# 2024_01_03_bar_IO_module.net
KiCad netlist of a schematic drawn in EasyEDA Pro
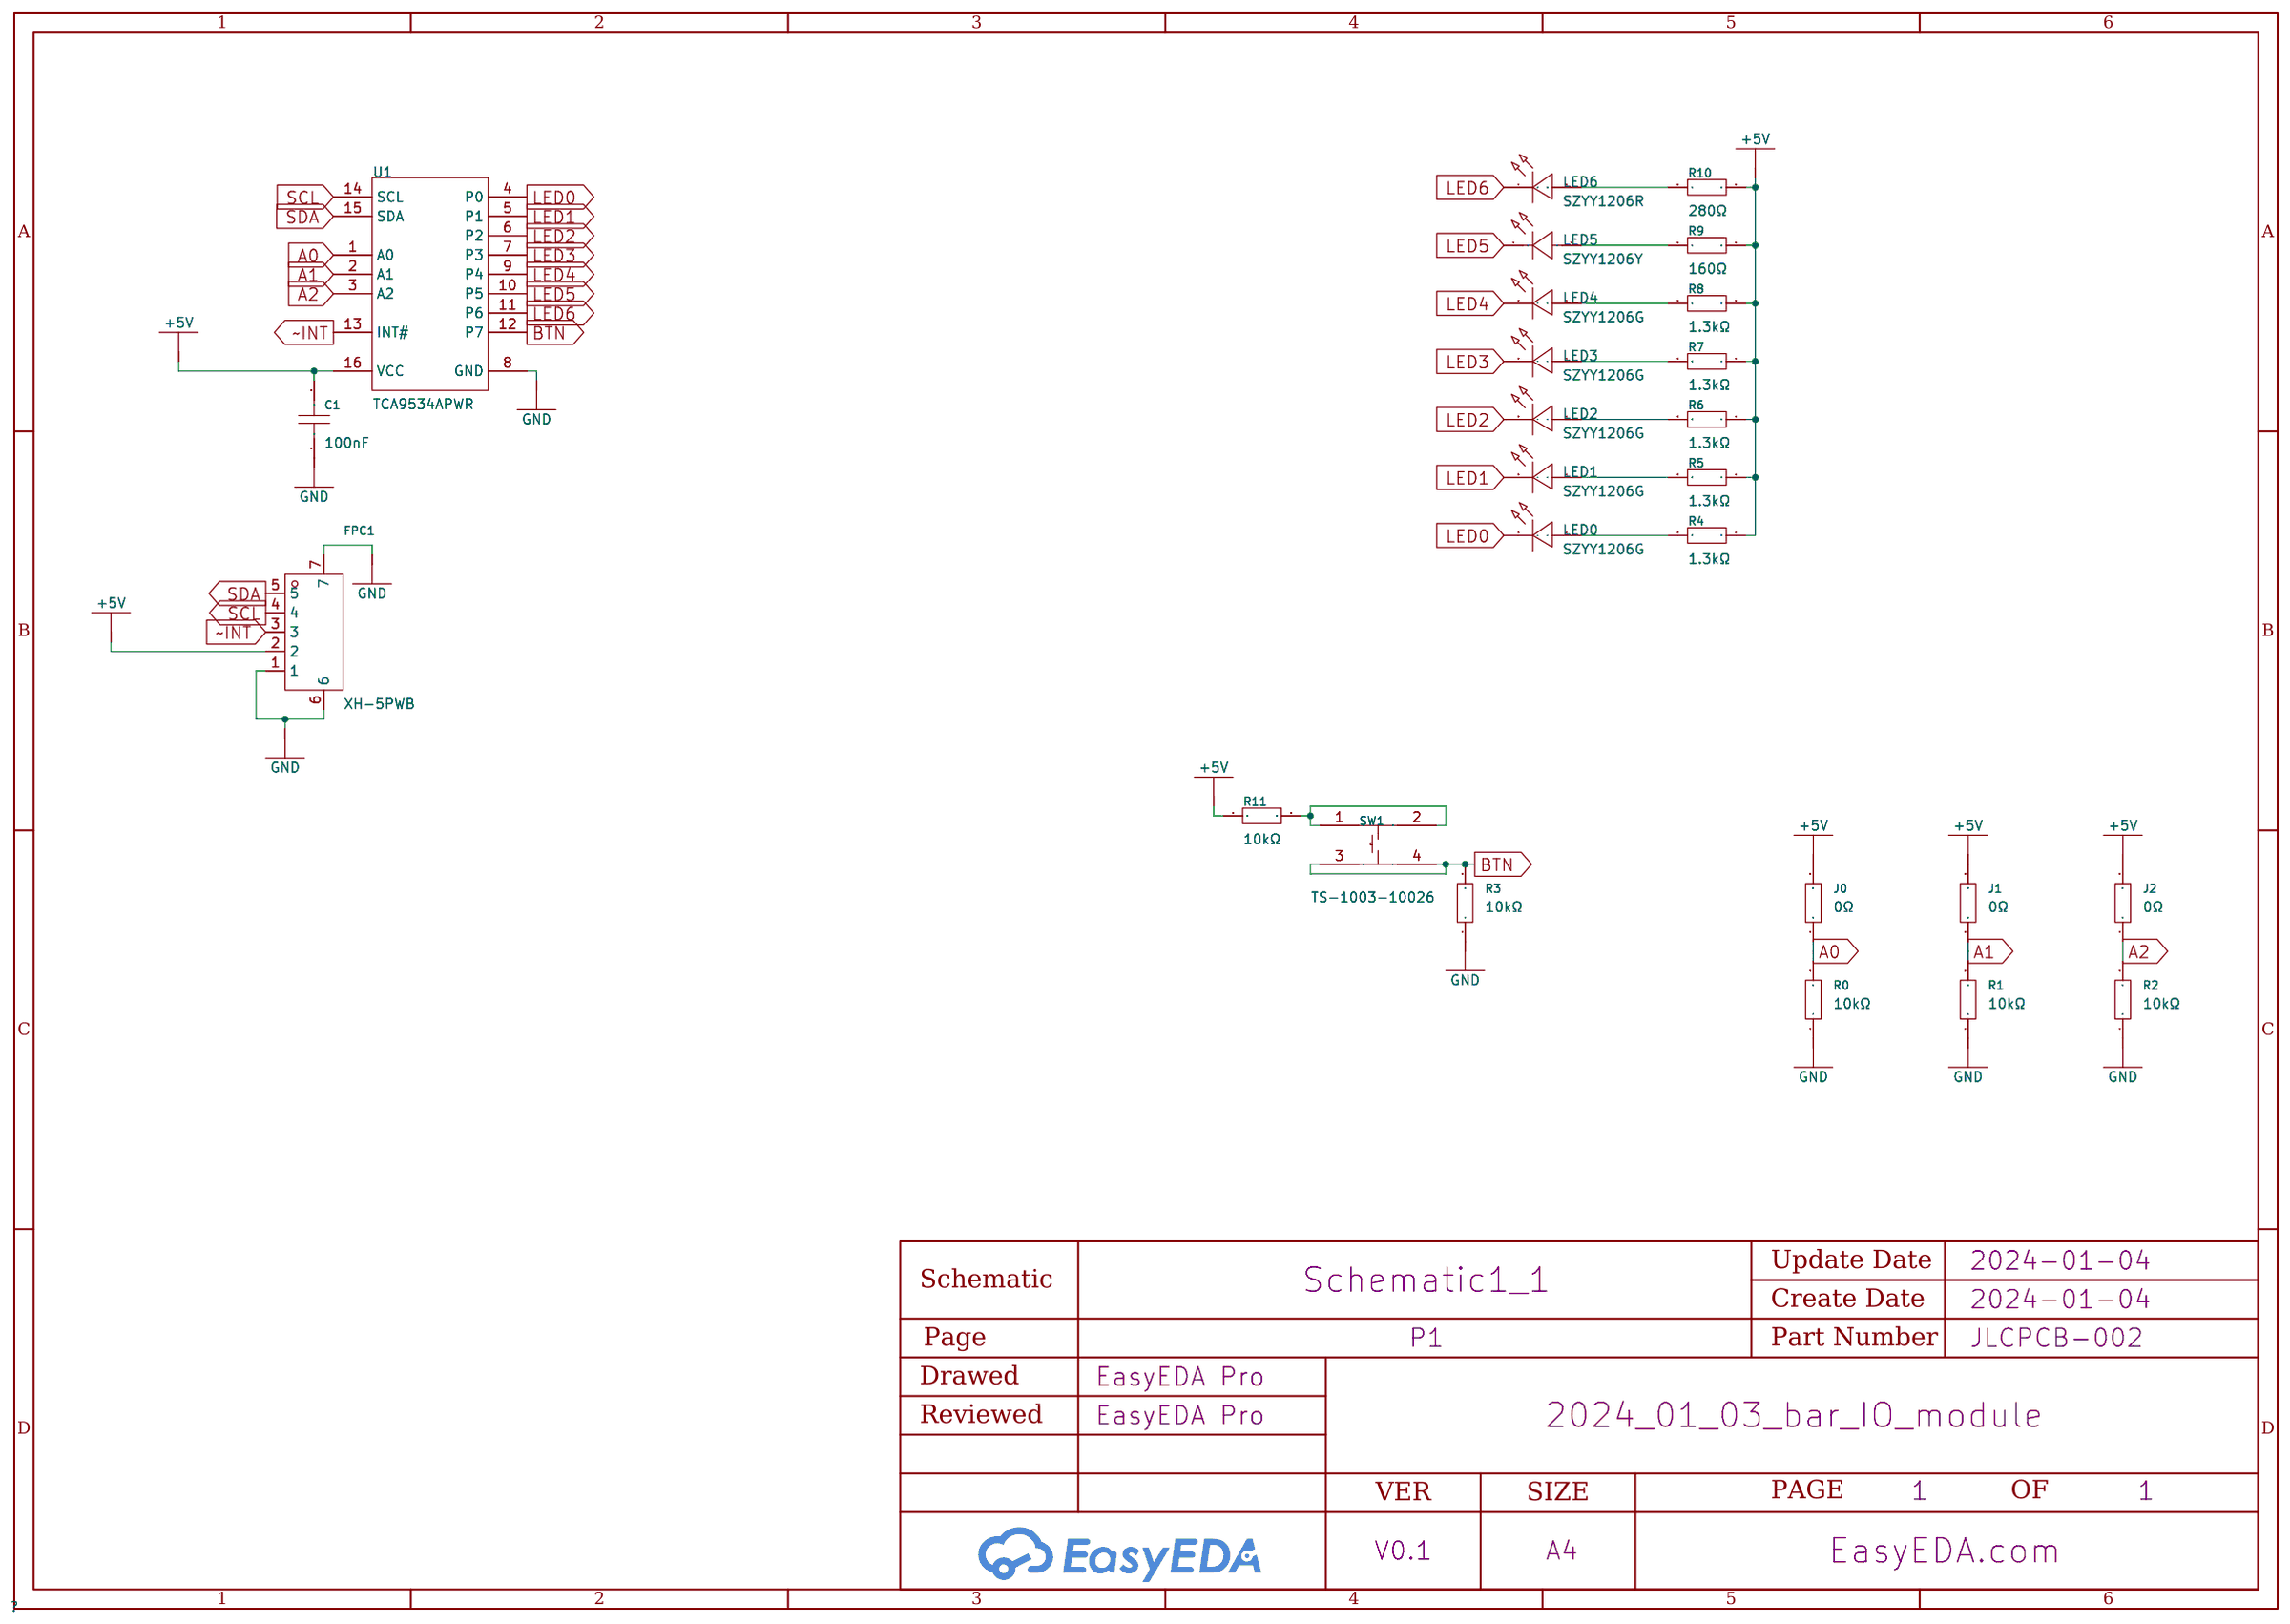
[diagram p0: schematic sheet]

(export (version "E")
  (design (tool "Eeschema 10.0.6"))
  (components
    (comp (ref "C1")
      (value "100nF")
      (footprint "easyedapro:C0603")
      (fields
        (field (name "Manufacturer Part") "HMK107B7104KAHT")
        (field (name "Manufacturer") "TAIYO YUDEN(太诱)")
      )
      (libsource (lib "easyedapro") (part "HMK107B7104KAHT"))
    )
    (comp (ref "FPC1")
      (value "XH-5PWB")
      (footprint "easyedapro:CONN-SMD_5P-P2.50_DEALON_XH-5PWB")
      (fields (field (name "Manufacturer") "DEALON(德艺隆)"))
      (libsource (lib "easyedapro") (part "XH-5PWB"))
    )
    (comp (ref "J0")
      (value "0Ω")
      (footprint "easyedapro:R0805")
      (fields
        (field (name "Manufacturer Part") "0805W8F1002T5E")
        (field (name "Manufacturer") "UNI-ROYAL(厚声)")
      )
      (libsource (lib "easyedapro") (part "0805W8F1002T5E"))
    )
    (comp (ref "J1")
      (value "0Ω")
      (footprint "easyedapro:R0805")
      (fields
        (field (name "Manufacturer Part") "0805W8F1002T5E")
        (field (name "Manufacturer") "UNI-ROYAL(厚声)")
      )
      (libsource (lib "easyedapro") (part "0805W8F1002T5E"))
    )
    (comp (ref "J2")
      (value "0Ω")
      (footprint "easyedapro:R0805")
      (fields
        (field (name "Manufacturer Part") "0805W8F1002T5E")
        (field (name "Manufacturer") "UNI-ROYAL(厚声)")
      )
      (libsource (lib "easyedapro") (part "0805W8F1002T5E"))
    )
    (comp (ref "LED0")
      (value "SZYY1206G")
      (footprint "easyedapro:LED1206-R-RD")
      (description "Emitted Color:Emerald")
      (fields (field (name "Manufacturer") "yongyu(永裕光电)"))
      (libsource (lib "easyedapro") (part "SZYY1206G"))
    )
    (comp (ref "LED1")
      (value "SZYY1206G")
      (footprint "easyedapro:LED1206-R-RD")
      (description "Emitted Color:Emerald")
      (fields (field (name "Manufacturer") "yongyu(永裕光电)"))
      (libsource (lib "easyedapro") (part "SZYY1206G"))
    )
    (comp (ref "LED2")
      (value "SZYY1206G")
      (footprint "easyedapro:LED1206-R-RD")
      (description "Emitted Color:Emerald")
      (fields (field (name "Manufacturer") "yongyu(永裕光电)"))
      (libsource (lib "easyedapro") (part "SZYY1206G"))
    )
    (comp (ref "LED3")
      (value "SZYY1206G")
      (footprint "easyedapro:LED1206-R-RD")
      (description "Emitted Color:Emerald")
      (fields (field (name "Manufacturer") "yongyu(永裕光电)"))
      (libsource (lib "easyedapro") (part "SZYY1206G"))
    )
    (comp (ref "LED4")
      (value "SZYY1206G")
      (footprint "easyedapro:LED1206-R-RD")
      (description "Emitted Color:Emerald")
      (fields (field (name "Manufacturer") "yongyu(永裕光电)"))
      (libsource (lib "easyedapro") (part "SZYY1206G"))
    )
    (comp (ref "LED5")
      (value "SZYY1206Y")
      (footprint "easyedapro:LED1206-R-RD")
      (fields (field (name "Manufacturer") "yongyu(永裕光电)"))
      (libsource (lib "easyedapro") (part "SZYY1206Y"))
    )
    (comp (ref "LED6")
      (value "SZYY1206R")
      (footprint "easyedapro:LED1206-R-RD")
      (fields (field (name "Manufacturer") "yongyu(永裕光电)"))
      (libsource (lib "easyedapro") (part "SZYY1206R"))
    )
    (comp (ref "R0")
      (value "10kΩ")
      (footprint "easyedapro:R0603")
      (fields
        (field (name "Manufacturer Part") "0603WAF1002T5E")
        (field (name "Manufacturer") "UNI-ROYAL(厚声)")
      )
      (libsource (lib "easyedapro") (part "0603WAF1002T5E"))
    )
    (comp (ref "R1")
      (value "10kΩ")
      (footprint "easyedapro:R0603")
      (fields
        (field (name "Manufacturer Part") "0603WAF1002T5E")
        (field (name "Manufacturer") "UNI-ROYAL(厚声)")
      )
      (libsource (lib "easyedapro") (part "0603WAF1002T5E"))
    )
    (comp (ref "R2")
      (value "10kΩ")
      (footprint "easyedapro:R0603")
      (fields
        (field (name "Manufacturer Part") "0603WAF1002T5E")
        (field (name "Manufacturer") "UNI-ROYAL(厚声)")
      )
      (libsource (lib "easyedapro") (part "0603WAF1002T5E"))
    )
    (comp (ref "R3")
      (value "10kΩ")
      (footprint "easyedapro:R0603")
      (fields
        (field (name "Manufacturer Part") "0603WAF1002T5E")
        (field (name "Manufacturer") "UNI-ROYAL(厚声)")
      )
      (libsource (lib "easyedapro") (part "0603WAF1002T5E"))
    )
    (comp (ref "R4")
      (value "1.3kΩ")
      (footprint "easyedapro:R0603")
      (fields
        (field (name "Manufacturer Part") "CQ03WAJ0132T5E")
        (field (name "Manufacturer") "UNI-ROYAL(厚声)")
      )
      (libsource (lib "easyedapro") (part "0603WAF1002T5E"))
    )
    (comp (ref "R5")
      (value "1.3kΩ")
      (footprint "easyedapro:R0603")
      (fields
        (field (name "Manufacturer Part") "CQ03WAJ0132T5E")
        (field (name "Manufacturer") "UNI-ROYAL(厚声)")
      )
      (libsource (lib "easyedapro") (part "0603WAF1002T5E"))
    )
    (comp (ref "R6")
      (value "1.3kΩ")
      (footprint "easyedapro:R0603")
      (fields
        (field (name "Manufacturer Part") "CQ03WAJ0132T5E")
        (field (name "Manufacturer") "UNI-ROYAL(厚声)")
      )
      (libsource (lib "easyedapro") (part "0603WAF1002T5E"))
    )
    (comp (ref "R7")
      (value "1.3kΩ")
      (footprint "easyedapro:R0603")
      (fields
        (field (name "Manufacturer Part") "CQ03WAJ0132T5E")
        (field (name "Manufacturer") "UNI-ROYAL(厚声)")
      )
      (libsource (lib "easyedapro") (part "0603WAF1002T5E"))
    )
    (comp (ref "R8")
      (value "1.3kΩ")
      (footprint "easyedapro:R0603")
      (fields
        (field (name "Manufacturer Part") "CQ03WAJ0132T5E")
        (field (name "Manufacturer") "UNI-ROYAL(厚声)")
      )
      (libsource (lib "easyedapro") (part "0603WAF1002T5E"))
    )
    (comp (ref "R9")
      (value "160Ω")
      (footprint "easyedapro:R0603")
      (fields
        (field (name "Manufacturer Part") "FRC0603J161 TS")
        (field (name "Manufacturer") "UNI-ROYAL(厚声)")
      )
      (libsource (lib "easyedapro") (part "0603WAF1002T5E"))
    )
    (comp (ref "R10")
      (value "280Ω")
      (footprint "easyedapro:R0603")
      (fields (field (name "Manufacturer Part") "ARG03BTC2800") (field (name "Manufacturer") "UNI-ROYAL(厚声)"))
      (libsource (lib "easyedapro") (part "0603WAF1002T5E"))
    )
    (comp (ref "R11")
      (value "10kΩ")
      (footprint "easyedapro:R0603")
      (fields
        (field (name "Manufacturer Part") "0603WAF1002T5E")
        (field (name "Manufacturer") "UNI-ROYAL(厚声)")
      )
      (libsource (lib "easyedapro") (part "0603WAF1002T5E"))
    )
    (comp (ref "SW1")
      (value "TS-1003-10026")
      (footprint "easyedapro:SW-TH_4P-L12.0-W12.0-P5.00-LS12.5")
      (fields (field (name "Manufacturer") "XUNPU(讯普)"))
      (libsource (lib "easyedapro") (part "TS-1003-10026"))
    )
    (comp (ref "U1")
      (value "TCA9534APWR")
      (footprint "easyedapro:TSSOP-16_L5.0-W4.4-P0.65-LS6.4-BL")
      (fields (field (name "Manufacturer") "TI(德州仪器)"))
      (libsource (lib "easyedapro") (part "TCA9534APWR"))
    )
  )
  (nets
    (net (code "1") (name "+5V") (class "Default")
      (node (ref "C1") (pin "2") (pinfunction "2_2") (pintype "input"))
      (node (ref "FPC1") (pin "2") (pinfunction "2_2") (pintype "input"))
      (node (ref "J0") (pin "2") (pinfunction "2_2") (pintype "input"))
      (node (ref "J1") (pin "2") (pinfunction "2_2") (pintype "input"))
      (node (ref "J2") (pin "2") (pinfunction "2_2") (pintype "input"))
      (node (ref "R10") (pin "1") (pinfunction "1_1") (pintype "input"))
      (node (ref "R11") (pin "1") (pinfunction "1_1") (pintype "input"))
      (node (ref "R4") (pin "1") (pinfunction "1_1") (pintype "input"))
      (node (ref "R5") (pin "1") (pinfunction "1_1") (pintype "input"))
      (node (ref "R6") (pin "1") (pinfunction "1_1") (pintype "input"))
      (node (ref "R7") (pin "1") (pinfunction "1_1") (pintype "input"))
      (node (ref "R8") (pin "1") (pinfunction "1_1") (pintype "input"))
      (node (ref "R9") (pin "1") (pinfunction "1_1") (pintype "input"))
      (node (ref "U1") (pin "16") (pinfunction "VCC_16") (pintype "input"))
    )
    (net (code "2") (name "A0") (class "Default")
      (node (ref "J0") (pin "1") (pinfunction "1_1") (pintype "input"))
      (node (ref "R0") (pin "2") (pinfunction "2_2") (pintype "input"))
      (node (ref "U1") (pin "1") (pinfunction "A0_1") (pintype "input"))
    )
    (net (code "3") (name "A1") (class "Default")
      (node (ref "J1") (pin "1") (pinfunction "1_1") (pintype "input"))
      (node (ref "R1") (pin "2") (pinfunction "2_2") (pintype "input"))
      (node (ref "U1") (pin "2") (pinfunction "A1_2") (pintype "input"))
    )
    (net (code "4") (name "A2") (class "Default")
      (node (ref "J2") (pin "1") (pinfunction "1_1") (pintype "input"))
      (node (ref "R2") (pin "2") (pinfunction "2_2") (pintype "input"))
      (node (ref "U1") (pin "3") (pinfunction "A2_3") (pintype "input"))
    )
    (net (code "5") (name "BTN") (class "Default")
      (node (ref "R3") (pin "2") (pinfunction "2_2") (pintype "input"))
      (node (ref "SW1") (pin "3") (pinfunction "3_3") (pintype "input"))
      (node (ref "SW1") (pin "4") (pinfunction "4_4") (pintype "input"))
      (node (ref "U1") (pin "12") (pinfunction "P7_12") (pintype "bidirectional"))
    )
    (net (code "6") (name "GND") (class "Default")
      (node (ref "C1") (pin "1") (pinfunction "1_1") (pintype "input"))
      (node (ref "FPC1") (pin "1") (pinfunction "1_1") (pintype "input"))
      (node (ref "FPC1") (pin "6") (pinfunction "6_6") (pintype "input"))
      (node (ref "FPC1") (pin "7") (pinfunction "7_7") (pintype "input"))
      (node (ref "R0") (pin "1") (pinfunction "1_1") (pintype "input"))
      (node (ref "R1") (pin "1") (pinfunction "1_1") (pintype "input"))
      (node (ref "R2") (pin "1") (pinfunction "1_1") (pintype "input"))
      (node (ref "R3") (pin "1") (pinfunction "1_1") (pintype "input"))
      (node (ref "U1") (pin "8") (pinfunction "GND_8") (pintype "input"))
    )
    (net (code "7") (name "LED0") (class "Default")
      (node (ref "LED0") (pin "2") (pinfunction "-_2") (pintype "input"))
      (node (ref "U1") (pin "4") (pinfunction "P0_4") (pintype "bidirectional"))
    )
    (net (code "8") (name "LED1") (class "Default")
      (node (ref "LED1") (pin "2") (pinfunction "-_2") (pintype "input"))
      (node (ref "U1") (pin "5") (pinfunction "P1_5") (pintype "bidirectional"))
    )
    (net (code "9") (name "LED2") (class "Default")
      (node (ref "LED2") (pin "2") (pinfunction "-_2") (pintype "input"))
      (node (ref "U1") (pin "6") (pinfunction "P2_6") (pintype "bidirectional"))
    )
    (net (code "10") (name "LED3") (class "Default")
      (node (ref "LED3") (pin "2") (pinfunction "-_2") (pintype "input"))
      (node (ref "U1") (pin "7") (pinfunction "P3_7") (pintype "bidirectional"))
    )
    (net (code "11") (name "LED4") (class "Default")
      (node (ref "LED4") (pin "2") (pinfunction "-_2") (pintype "input"))
      (node (ref "U1") (pin "9") (pinfunction "P4_9") (pintype "bidirectional"))
    )
    (net (code "12") (name "LED5") (class "Default")
      (node (ref "LED5") (pin "1") (pinfunction "K_1") (pintype "input"))
      (node (ref "U1") (pin "10") (pinfunction "P5_10") (pintype "bidirectional"))
    )
    (net (code "13") (name "LED6") (class "Default")
      (node (ref "LED6") (pin "1") (pinfunction "1_1") (pintype "input"))
      (node (ref "U1") (pin "11") (pinfunction "P6_11") (pintype "bidirectional"))
    )
    (net (code "14") (name "Net-(LED0-+)") (class "Default")
      (node (ref "LED0") (pin "1") (pinfunction "+_1") (pintype "input"))
      (node (ref "R4") (pin "2") (pinfunction "2_2") (pintype "input"))
    )
    (net (code "15") (name "Net-(LED1-+)") (class "Default")
      (node (ref "LED1") (pin "1") (pinfunction "+_1") (pintype "input"))
      (node (ref "R5") (pin "2") (pinfunction "2_2") (pintype "input"))
    )
    (net (code "16") (name "Net-(LED2-+)") (class "Default")
      (node (ref "LED2") (pin "1") (pinfunction "+_1") (pintype "input"))
      (node (ref "R6") (pin "2") (pinfunction "2_2") (pintype "input"))
    )
    (net (code "17") (name "Net-(LED3-+)") (class "Default")
      (node (ref "LED3") (pin "1") (pinfunction "+_1") (pintype "input"))
      (node (ref "R7") (pin "2") (pinfunction "2_2") (pintype "input"))
    )
    (net (code "18") (name "Net-(LED4-+)") (class "Default")
      (node (ref "LED4") (pin "1") (pinfunction "+_1") (pintype "input"))
      (node (ref "R8") (pin "2") (pinfunction "2_2") (pintype "input"))
    )
    (net (code "19") (name "Net-(LED5-A)") (class "Default")
      (node (ref "LED5") (pin "2") (pinfunction "A_2") (pintype "input"))
      (node (ref "R9") (pin "2") (pinfunction "2_2") (pintype "input"))
    )
    (net (code "20") (name "Net-(LED6-Pad2)") (class "Default")
      (node (ref "LED6") (pin "2") (pinfunction "2_2") (pintype "input"))
      (node (ref "R10") (pin "2") (pinfunction "2_2") (pintype "input"))
    )
    (net (code "21") (name "Net-(R11-Pad2)") (class "Default")
      (node (ref "R11") (pin "2") (pinfunction "2_2") (pintype "input"))
      (node (ref "SW1") (pin "1") (pinfunction "1_1") (pintype "input"))
      (node (ref "SW1") (pin "2") (pinfunction "2_2") (pintype "input"))
    )
    (net (code "22") (name "SCL") (class "Default")
      (node (ref "FPC1") (pin "4") (pinfunction "4_4") (pintype "input"))
      (node (ref "U1") (pin "14") (pinfunction "SCL_14") (pintype "input"))
    )
    (net (code "23") (name "SDA") (class "Default")
      (node (ref "FPC1") (pin "5") (pinfunction "5_5") (pintype "input"))
      (node (ref "U1") (pin "15") (pinfunction "SDA_15") (pintype "bidirectional"))
    )
    (net (code "24") (name "~INT") (class "Default")
      (node (ref "FPC1") (pin "3") (pinfunction "3_3") (pintype "input"))
      (node (ref "U1") (pin "13") (pinfunction "INT#_13") (pintype "input"))
    )
  )
)
